# TPS65130.net
KiCad netlist of a schematic drawn in Altium Designer
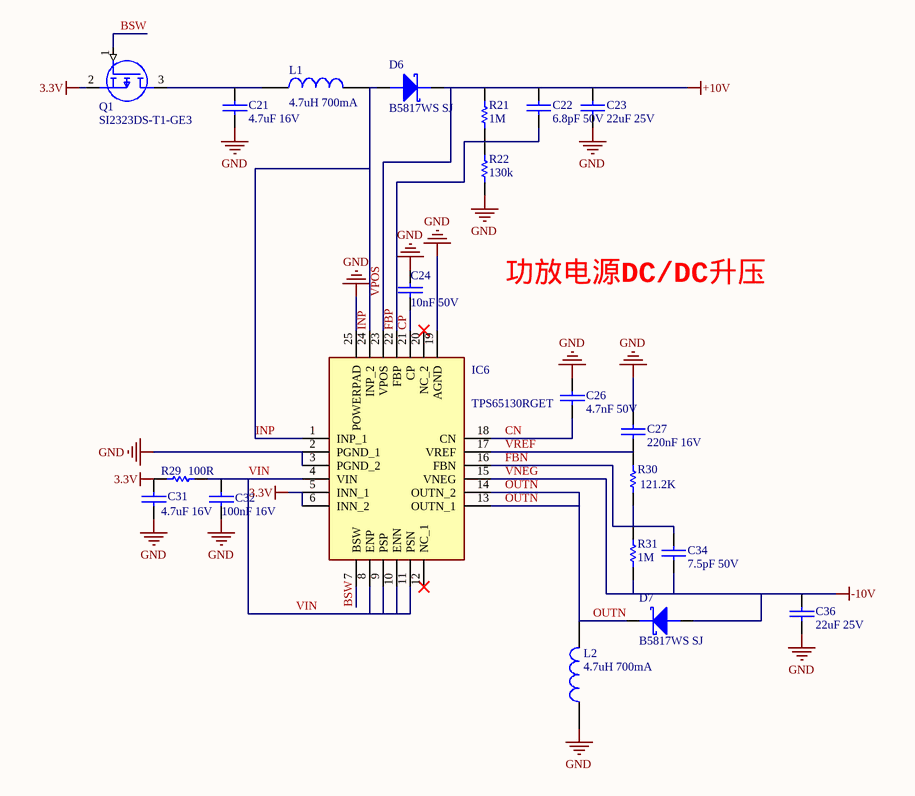
[diagram p0: TPS65130.schdoc]

(export (version "E")
  (design (tool "Eeschema 10.0.6"))
  (components
    (comp (ref "C21") (value "4.7uF 16V") (footprint "0603C") (libsource (lib "电容") (part "CAP-NP")))
    (comp (ref "C22") (value "6.8pF 50V") (footprint "0402C") (libsource (lib "电容") (part "CAP-NP")))
    (comp (ref "C23") (value "22uF 25V") (footprint "0805C") (libsource (lib "电容") (part "CAP-NP")))
    (comp (ref "C24") (value "10nF 50V") (footprint "0402C") (libsource (lib "电容") (part "CAP-NP")))
    (comp (ref "C26") (value "4.7nF 50V") (footprint "0402C") (libsource (lib "电容") (part "CAP-NP")))
    (comp (ref "C27") (value "220nF 16V") (footprint "0402C") (libsource (lib "电容") (part "CAP-NP")))
    (comp (ref "C31") (value "4.7uF 16V") (footprint "0603C") (libsource (lib "电容") (part "CAP-NP")))
    (comp (ref "C32")
      (value "100nF 16V")
      (footprint "0402C")
      (fields (field (name "TOLERANCE") "10%") (field (name "VOLTAGE") "16V"))
      (libsource (lib "电容") (part "CAP-NP"))
    )
    (comp (ref "C34") (value "7.5pF 50V") (footprint "0402C") (libsource (lib "电容") (part "CAP-NP")))
    (comp (ref "C36") (value "22uF 25V") (footprint "0805C") (libsource (lib "电容") (part "CAP-NP")))
    (comp (ref "D6")
      (value "B5817WS SJ")
      (footprint "SOD-323")
      (description "肖特基二极管")
      (libsource (lib "二极管") (part "DIODE SCHOTTKY"))
    )
    (comp (ref "D7")
      (value "B5817WS SJ")
      (footprint "SOD-323")
      (description "肖特基二极管")
      (libsource (lib "二极管") (part "DIODE SCHOTTKY"))
    )
    (comp (ref "IC6")
      (value "TPS65130RGET")
      (footprint "SamacSys:QFN50P400X400X100-25N")
      (description "DC/DC 芯片")
      (fields
        (field (name "MANUFACTURER_PART_NUMBER") "TPS65131RGET")
        (field (name "MOUSER PART NUMBER") "595-TPS65131RGET")
      )
      (libsource (lib "*") (part "TPS65131RGET"))
    )
    (comp (ref "L1")
      (value "4.7uH 700mA")
      (footprint "0805L")
      (description "MLP2012S4R7MT0S1")
      (libsource (lib "") (part "INDUCTOR_1"))
    )
    (comp (ref "L2")
      (value "4.7uH 700mA")
      (footprint "0805L")
      (description "MLP2012S4R7MT0S1")
      (libsource (lib "Inductance") (part "INDUCTOR"))
    )
    (comp (ref "Q1")
      (value "SI2323DS-T1-GE3")
      (footprint "SamacSys:SOT95P237X112-3N")
      (description "MOSFET (P-Channel)")
      (fields (field (name "MOUSER PART NUMBER") "781-SI2323DS-T1-GE3"))
      (libsource (lib "*") (part "SI2323DS-T1-GE3"))
    )
    (comp (ref "R21") (value "1M") (footprint "0402R") (libsource (lib "Resistor") (part "RES")))
    (comp (ref "R22") (value "130k") (footprint "0402R") (libsource (lib "Resistor") (part "RES")))
    (comp (ref "R29") (value "100R") (footprint "0402R") (libsource (lib "Resistor") (part "RES")))
    (comp (ref "R30") (value "121.2K") (footprint "0402R") (libsource (lib "Resistor") (part "RES")))
    (comp (ref "R31") (value "1M") (footprint "0402R") (libsource (lib "Resistor") (part "RES")))
  )
  (nets
    (net (code "1") (name "+10V") (class "Default")
      (node (ref "C22") (pin "2") (pinfunction "2_2") (pintype "passive"))
      (node (ref "C23") (pin "1") (pinfunction "1_1") (pintype "passive"))
      (node (ref "D6") (pin "K") (pinfunction "K_K") (pintype "passive"))
      (node (ref "IC6") (pin "23") (pinfunction "VPOS_23") (pintype "passive"))
      (node (ref "R21") (pin "2") (pinfunction "2_2") (pintype "passive"))
    )
    (net (code "2") (name "-10V") (class "Default")
      (node (ref "C34") (pin "1") (pinfunction "1_1") (pintype "passive"))
      (node (ref "C36") (pin "1") (pinfunction "1_1") (pintype "passive"))
      (node (ref "D7") (pin "A") (pinfunction "A_A") (pintype "passive"))
      (node (ref "IC6") (pin "15") (pinfunction "VNEG_15") (pintype "passive"))
      (node (ref "R31") (pin "1") (pinfunction "1_1") (pintype "passive"))
    )
    (net (code "3") (name "/BSW") (class "Default")
      (node (ref "IC6") (pin "7") (pinfunction "BSW_7") (pintype "passive"))
      (node (ref "Q1") (pin "1") (pinfunction "G_1") (pintype "input"))
    )
    (net (code "4") (name "/CN") (class "Default")
      (node (ref "C26") (pin "2") (pinfunction "2_2") (pintype "passive"))
      (node (ref "IC6") (pin "18") (pinfunction "CN_18") (pintype "passive"))
    )
    (net (code "5") (name "/CP") (class "Default")
      (node (ref "C24") (pin "2") (pinfunction "2_2") (pintype "passive"))
      (node (ref "IC6") (pin "21") (pinfunction "CP_21") (pintype "passive"))
    )
    (net (code "6") (name "/FBN") (class "Default")
      (node (ref "C34") (pin "2") (pinfunction "2_2") (pintype "passive"))
      (node (ref "IC6") (pin "16") (pinfunction "FBN_16") (pintype "passive"))
      (node (ref "R30") (pin "1") (pinfunction "1_1") (pintype "passive"))
      (node (ref "R31") (pin "2") (pinfunction "2_2") (pintype "passive"))
    )
    (net (code "7") (name "/FBP") (class "Default")
      (node (ref "C22") (pin "1") (pinfunction "1_1") (pintype "passive"))
      (node (ref "IC6") (pin "22") (pinfunction "FBP_22") (pintype "passive"))
      (node (ref "R21") (pin "1") (pinfunction "1_1") (pintype "passive"))
      (node (ref "R22") (pin "2") (pinfunction "2_2") (pintype "passive"))
    )
    (net (code "8") (name "/INP") (class "Default")
      (node (ref "D6") (pin "A") (pinfunction "A_A") (pintype "passive"))
      (node (ref "IC6") (pin "1") (pinfunction "INP_1_1") (pintype "passive"))
      (node (ref "IC6") (pin "24") (pinfunction "INP_2_24") (pintype "passive"))
      (node (ref "L1") (pin "2") (pinfunction "2_2") (pintype "passive"))
    )
    (net (code "9") (name "/OUTN") (class "Default")
      (node (ref "D7") (pin "K") (pinfunction "K_K") (pintype "passive"))
      (node (ref "IC6") (pin "13") (pinfunction "OUTN_1_13") (pintype "passive"))
      (node (ref "IC6") (pin "14") (pinfunction "OUTN_2_14") (pintype "passive"))
      (node (ref "L2") (pin "2") (pinfunction "2_2") (pintype "passive"))
    )
    (net (code "10") (name "/VIN") (class "Default")
      (node (ref "C32") (pin "1") (pinfunction "1_1") (pintype "passive"))
      (node (ref "IC6") (pin "10") (pinfunction "ENN_10") (pintype "passive"))
      (node (ref "IC6") (pin "11") (pinfunction "PSN_11") (pintype "passive"))
      (node (ref "IC6") (pin "4") (pinfunction "VIN_4") (pintype "passive"))
      (node (ref "IC6") (pin "8") (pinfunction "ENP_8") (pintype "passive"))
      (node (ref "IC6") (pin "9") (pinfunction "PSP_9") (pintype "passive"))
      (node (ref "R29") (pin "2") (pinfunction "2_2") (pintype "passive"))
    )
    (net (code "11") (name "/VREF") (class "Default")
      (node (ref "C27") (pin "1") (pinfunction "1_1") (pintype "passive"))
      (node (ref "IC6") (pin "17") (pinfunction "VREF_17") (pintype "passive"))
      (node (ref "R30") (pin "2") (pinfunction "2_2") (pintype "passive"))
    )
    (net (code "12") (name "3.3V") (class "Default")
      (node (ref "C31") (pin "2") (pinfunction "2_2") (pintype "passive"))
      (node (ref "IC6") (pin "5") (pinfunction "INN_1_5") (pintype "passive"))
      (node (ref "IC6") (pin "6") (pinfunction "INN_2_6") (pintype "passive"))
      (node (ref "Q1") (pin "2") (pinfunction "S_2") (pintype "passive"))
      (node (ref "R29") (pin "1") (pinfunction "1_1") (pintype "passive"))
    )
    (net (code "13") (name "GND") (class "Default")
      (node (ref "C21") (pin "1") (pinfunction "1_1") (pintype "passive"))
      (node (ref "C23") (pin "2") (pinfunction "2_2") (pintype "passive"))
      (node (ref "C24") (pin "1") (pinfunction "1_1") (pintype "passive"))
      (node (ref "C26") (pin "1") (pinfunction "1_1") (pintype "passive"))
      (node (ref "C27") (pin "2") (pinfunction "2_2") (pintype "passive"))
      (node (ref "C31") (pin "1") (pinfunction "1_1") (pintype "passive"))
      (node (ref "C32") (pin "2") (pinfunction "2_2") (pintype "passive"))
      (node (ref "C36") (pin "2") (pinfunction "2_2") (pintype "passive"))
      (node (ref "IC6") (pin "19") (pinfunction "AGND_19") (pintype "passive"))
      (node (ref "IC6") (pin "2") (pinfunction "PGND_1_2") (pintype "passive"))
      (node (ref "IC6") (pin "25") (pinfunction "POWERPAD_25") (pintype "passive"))
      (node (ref "IC6") (pin "3") (pinfunction "PGND_2_3") (pintype "passive"))
      (node (ref "L2") (pin "1") (pinfunction "1_1") (pintype "passive"))
      (node (ref "R22") (pin "1") (pinfunction "1_1") (pintype "passive"))
    )
    (net (code "14") (name "Net-(Q1-D)") (class "Default")
      (node (ref "C21") (pin "2") (pinfunction "2_2") (pintype "passive"))
      (node (ref "L1") (pin "1") (pinfunction "1_1") (pintype "passive"))
      (node (ref "Q1") (pin "3") (pinfunction "D_3") (pintype "passive"))
    )
    (net (code "15") (name "unconnected-(IC6-NC_1-Pad12)") (class "Default")
      (node (ref "IC6") (pin "12") (pinfunction "NC_1_12") (pintype "passive+no_connect"))
    )
    (net (code "16") (name "unconnected-(IC6-NC_2-Pad20)") (class "Default")
      (node (ref "IC6") (pin "20") (pinfunction "NC_2_20") (pintype "passive+no_connect"))
    )
  )
)
